# USB.net
KiCad netlist of a schematic drawn in Altium Designer
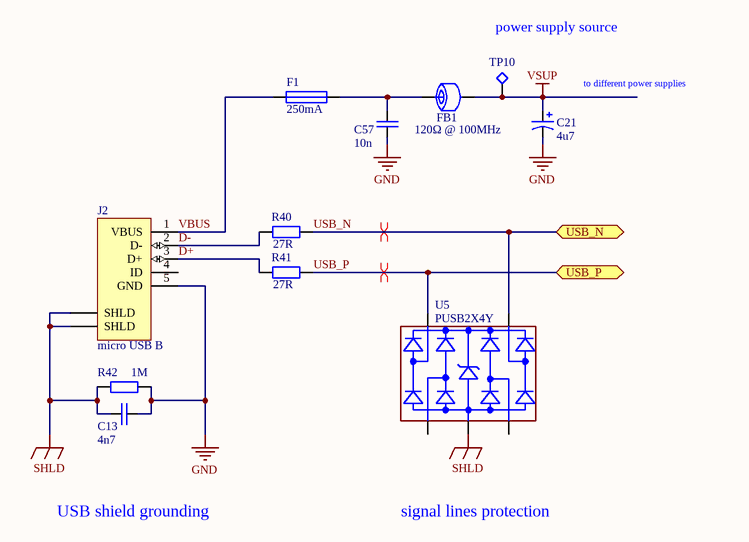
[diagram p0: USB.SchDoc]

(export (version "E")
  (design (tool "Eeschema 10.0.6"))
  (components
    (comp (ref "C13")
      (value "4n7")
      (footprint "C_0603")
      (description "Generic capacitor")
      (fields (field (name "Comment") "comment"))
      (libsource (lib "DAQ") (part "Capacitor"))
    )
    (comp (ref "C21")
      (value "4u7")
      (footprint "Tantalum Case A")
      (description "Generic polarized capacitor")
      (fields (field (name "Comment") "comment"))
      (libsource (lib "DAQ") (part "Capacitor - polarized"))
    )
    (comp (ref "C57")
      (value "10n")
      (footprint "C_0603")
      (description "Generic capacitor")
      (fields (field (name "Comment") "comment"))
      (libsource (lib "DAQ") (part "Capacitor"))
    )
    (comp (ref "F1")
      (value "250mA")
      (footprint "PPTCF 1206")
      (description "Resettable Fuse, PPTC, 1206 (3216 Metric), POLYFUSE 1206L Series, 16 VDC, 250 mA, 500 mA, 0.08 s")
      (fields (field (name "MANUFACTURER") "Littelfuse"))
      (libsource (lib "DAQ") (part "1206L025YR"))
    )
    (comp (ref "FB1")
      (value "120Ω @ 100MHz")
      (footprint "SMD_0805")
      (description "Ferrite Bead, 0805 [2012 Metric], 120 ohm, 800 mA, BLM21A Series, 0.15 ohm, ± 25%")
      (fields (field (name "MANUFACTURER") "Murata"))
      (libsource (lib "DAQ") (part "BLM21AG121SN1D"))
    )
    (comp (ref "J2")
      (value "micro USB B")
      (footprint "MICRO_USB_A")
      (description "USB Connector, Micro USB Type AB, USB 2.0, Receptacle, 5 Ways, Surface Mount, Right Angle")
      (fields (field (name "MANUFACTURER") "FCI"))
      (libsource (lib "DAQ") (part "10104111-0001LF"))
    )
    (comp (ref "R40")
      (value "27R")
      (footprint "R_0603")
      (description "Generic resistor")
      (fields (field (name "Comment") "comment"))
      (libsource (lib "DAQ") (part "Resistor"))
    )
    (comp (ref "R41")
      (value "27R")
      (footprint "R_0603")
      (description "Generic resistor")
      (fields (field (name "Comment") "comment"))
      (libsource (lib "DAQ") (part "Resistor"))
    )
    (comp (ref "R42")
      (value "1M")
      (footprint "R_0603")
      (description "Generic resistor")
      (fields (field (name "Comment") "comment"))
      (libsource (lib "DAQ") (part "Resistor"))
    )
    (comp (ref "TP10")
      (value "testpoint")
      (footprint "TP1_FULL")
      (description "testpoint 1.5mm diameter no hole")
      (fields (field (name "PART NUMBER") "XXC0006"))
      (libsource (lib "DAQ") (part "Test Point"))
    )
    (comp (ref "U5")
      (value "PUSB2X4Y")
      (footprint "SOT363")
      (description "ESD protection for high-speed interfaces")
      (fields (field (name "PART NUMBER") "XDE0000") (field (name "MANUFACTURER") "Multicomp"))
      (libsource (lib "DAQ") (part "PUSB2X4Y"))
    )
  )
  (nets
    (net (code "1") (name "/D+") (class "Default")
      (node (ref "J2") (pin "3") (pinfunction "D+_3") (pintype "bidirectional"))
      (node (ref "R41") (pin "1") (pintype "passive"))
    )
    (net (code "2") (name "/D-") (class "Default")
      (node (ref "J2") (pin "2") (pinfunction "D-_2") (pintype "bidirectional"))
      (node (ref "R40") (pin "1") (pintype "passive"))
    )
    (net (code "3") (name "/USB_N") (class "Default")
      (node (ref "R40") (pin "2") (pintype "passive"))
      (node (ref "U5") (pin "4") (pinfunction "4_4") (pintype "passive"))
    )
    (net (code "4") (name "/USB_P") (class "Default")
      (node (ref "R41") (pin "2") (pintype "passive"))
      (node (ref "U5") (pin "6") (pinfunction "6_6") (pintype "passive"))
    )
    (net (code "5") (name "/VBUS") (class "Default")
      (node (ref "F1") (pin "1") (pinfunction "1_1") (pintype "passive"))
      (node (ref "J2") (pin "1") (pinfunction "VBUS_1") (pintype "power_in"))
    )
    (net (code "6") (name "GND") (class "Default")
      (node (ref "C13") (pin "1") (pinfunction "1_1") (pintype "passive"))
      (node (ref "C21") (pin "2") (pinfunction "2_2") (pintype "passive"))
      (node (ref "C57") (pin "2") (pinfunction "2_2") (pintype "passive"))
      (node (ref "J2") (pin "5") (pinfunction "GND_5") (pintype "power_in"))
      (node (ref "R42") (pin "1") (pintype "passive"))
    )
    (net (code "7") (name "Net-(C57-Pad1)") (class "Default")
      (node (ref "C57") (pin "1") (pinfunction "1_1") (pintype "passive"))
      (node (ref "F1") (pin "2") (pinfunction "2_2") (pintype "passive"))
      (node (ref "FB1") (pin "1") (pintype "passive"))
    )
    (net (code "8") (name "SHLD") (class "Default")
      (node (ref "C13") (pin "2") (pinfunction "2_2") (pintype "passive"))
      (node (ref "J2") (pin "6") (pinfunction "SHLD_6") (pintype "passive"))
      (node (ref "J2") (pin "7") (pinfunction "SHLD_7") (pintype "passive"))
      (node (ref "R42") (pin "2") (pintype "passive"))
      (node (ref "U5") (pin "2") (pinfunction "2_2") (pintype "passive"))
    )
    (net (code "9") (name "VSUP") (class "Default")
      (node (ref "C21") (pin "1") (pinfunction "1_1") (pintype "passive"))
      (node (ref "FB1") (pin "2") (pintype "passive"))
      (node (ref "TP10") (pin "1") (pinfunction "1_1") (pintype "passive"))
    )
    (net (code "10") (name "unconnected-(J2-ID-Pad4)") (class "Default")
      (node (ref "J2") (pin "4") (pinfunction "ID_4") (pintype "passive"))
    )
    (net (code "11") (name "unconnected-(U5-Pad1)") (class "Default")
      (node (ref "U5") (pin "1") (pinfunction "1_1") (pintype "passive"))
    )
    (net (code "12") (name "unconnected-(U5-Pad3)") (class "Default")
      (node (ref "U5") (pin "3") (pinfunction "3_3") (pintype "passive"))
    )
  )
)
